# BigBus_Error.net
KiCad netlist of a schematic drawn in EAGLE
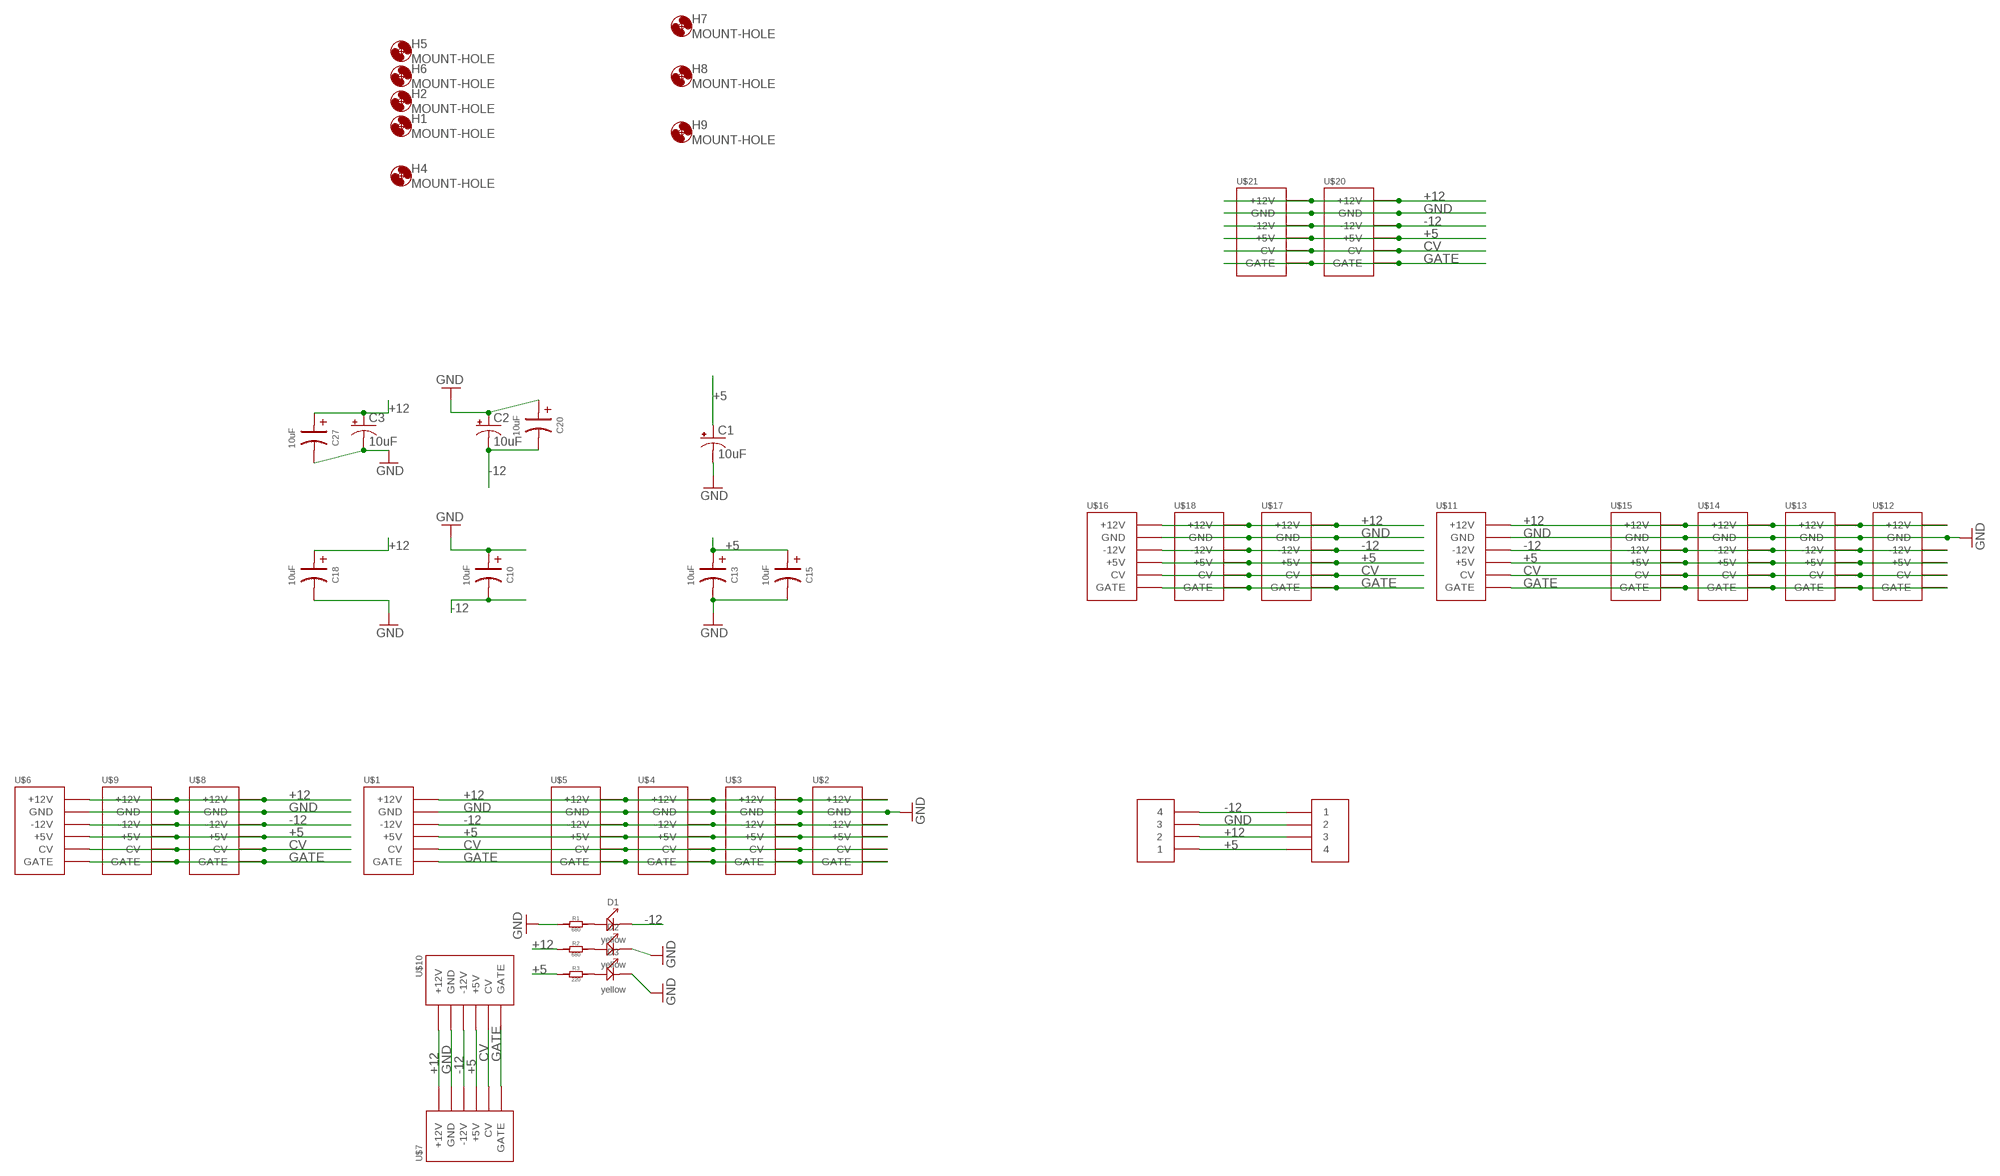
[diagram p0: schematic, sheet 1]

(export (version "E")
  (design (tool "Eeschema 10.0.6"))
  (components
    (comp (ref "C1")
      (value "10uF")
      (footprint "eagle-import:PANASONIC_D")
      (libsource (lib "eagle-import") (part "CAP_POLD"))
    )
    (comp (ref "C2")
      (value "10uF")
      (footprint "eagle-import:PANASONIC_D")
      (libsource (lib "eagle-import") (part "CAP_POLD"))
    )
    (comp (ref "C3")
      (value "10uF")
      (footprint "eagle-import:PANASONIC_D")
      (libsource (lib "eagle-import") (part "CAP_POLD"))
    )
    (comp (ref "C10")
      (value "10uF")
      (footprint "eagle-import:CASE-A_3216")
      (libsource (lib "eagle-import") (part "C-POLAR-A"))
    )
    (comp (ref "C13")
      (value "10uF")
      (footprint "eagle-import:CASE-A_3216")
      (libsource (lib "eagle-import") (part "C-POLAR-A"))
    )
    (comp (ref "C15")
      (value "10uF")
      (footprint "eagle-import:CASE-A_3216")
      (libsource (lib "eagle-import") (part "C-POLAR-A"))
    )
    (comp (ref "C18")
      (value "10uF")
      (footprint "eagle-import:CASE-A_3216")
      (libsource (lib "eagle-import") (part "C-POLAR-A"))
    )
    (comp (ref "C20")
      (value "10uF")
      (footprint "eagle-import:CASE-A_3216")
      (libsource (lib "eagle-import") (part "C-POLAR-A"))
    )
    (comp (ref "C27")
      (value "10uF")
      (footprint "eagle-import:CASE-A_3216")
      (libsource (lib "eagle-import") (part "C-POLAR-A"))
    )
    (comp (ref "D1")
      (value "yellow")
      (footprint "eagle-import:LED0603")
      (libsource (lib "eagle-import") (part "LED"))
    )
    (comp (ref "D2")
      (value "yellow")
      (footprint "eagle-import:LED0603")
      (libsource (lib "eagle-import") (part "LED"))
    )
    (comp (ref "D3")
      (value "yellow")
      (footprint "eagle-import:LED0603")
      (libsource (lib "eagle-import") (part "LED"))
    )
    (comp (ref "H1")
      (value "MOUNT-HOLE")
      (footprint "eagle-import:3.2-NOMARKINGS-SMALLSAFEZONE")
      (libsource (lib "eagle-import") (part "MOUNT-HOLE"))
    )
    (comp (ref "H2")
      (value "MOUNT-HOLE")
      (footprint "eagle-import:3.2-NOMARKINGS-SMALLSAFEZONE")
      (libsource (lib "eagle-import") (part "MOUNT-HOLE"))
    )
    (comp (ref "H4")
      (value "MOUNT-HOLE")
      (footprint "eagle-import:3.2-NOMARKINGS-SMALLSAFEZONE")
      (libsource (lib "eagle-import") (part "MOUNT-HOLE"))
    )
    (comp (ref "H5")
      (value "MOUNT-HOLE")
      (footprint "eagle-import:3.2-NOMARKINGS-SMALLSAFEZONE")
      (libsource (lib "eagle-import") (part "MOUNT-HOLE"))
    )
    (comp (ref "H6")
      (value "MOUNT-HOLE")
      (footprint "eagle-import:3.2-NOMARKINGS-SMALLSAFEZONE")
      (libsource (lib "eagle-import") (part "MOUNT-HOLE"))
    )
    (comp (ref "H7")
      (value "MOUNT-HOLE")
      (footprint "eagle-import:3.2-NOMARKINGS-SMALLSAFEZONE")
      (libsource (lib "eagle-import") (part "MOUNT-HOLE"))
    )
    (comp (ref "H8")
      (value "MOUNT-HOLE")
      (footprint "eagle-import:3.2-NOMARKINGS-SMALLSAFEZONE")
      (libsource (lib "eagle-import") (part "MOUNT-HOLE"))
    )
    (comp (ref "H9")
      (value "MOUNT-HOLE")
      (footprint "eagle-import:3.2-NOMARKINGS-SMALLSAFEZONE")
      (libsource (lib "eagle-import") (part "MOUNT-HOLE"))
    )
    (comp (ref "R1")
      (value "680")
      (footprint "eagle-import:R0603")
      (libsource (lib "eagle-import") (part "R-0603"))
    )
    (comp (ref "R2")
      (value "680")
      (footprint "eagle-import:R0603")
      (libsource (lib "eagle-import") (part "R-0603"))
    )
    (comp (ref "R3")
      (value "220")
      (footprint "eagle-import:R0603")
      (libsource (lib "eagle-import") (part "R-0603"))
    )
    (comp (ref "U$1")
      (value "POWER_SHROUDED_NOTEXT")
      (footprint "eagle-import:POWER_16_SHROUDED_NOTEXT")
      (libsource (lib "eagle-import") (part "POWER_SHROUDED_NOTEXT"))
    )
    (comp (ref "U$2")
      (value "POWER_SHROUDED_NOTEXT")
      (footprint "eagle-import:POWER_16_SHROUDED_NOTEXT")
      (libsource (lib "eagle-import") (part "POWER_SHROUDED_NOTEXT"))
    )
    (comp (ref "U$3")
      (value "POWER_SHROUDED_NOTEXT")
      (footprint "eagle-import:POWER_16_SHROUDED_NOTEXT")
      (libsource (lib "eagle-import") (part "POWER_SHROUDED_NOTEXT"))
    )
    (comp (ref "U$4")
      (value "POWER_SHROUDED_NOTEXT")
      (footprint "eagle-import:POWER_16_SHROUDED_NOTEXT")
      (libsource (lib "eagle-import") (part "POWER_SHROUDED_NOTEXT"))
    )
    (comp (ref "U$5")
      (value "POWER_SHROUDED_NOTEXT")
      (footprint "eagle-import:POWER_16_SHROUDED_NOTEXT")
      (libsource (lib "eagle-import") (part "POWER_SHROUDED_NOTEXT"))
    )
    (comp (ref "U$6")
      (value "POWER_SHROUDED_NOTEXT")
      (footprint "eagle-import:POWER_16_SHROUDED_NOTEXT")
      (libsource (lib "eagle-import") (part "POWER_SHROUDED_NOTEXT"))
    )
    (comp (ref "U$7")
      (value "POWER_SHROUDED_NOTEXT")
      (footprint "eagle-import:POWER_16_SHROUDED_NOTEXT")
      (libsource (lib "eagle-import") (part "POWER_SHROUDED_NOTEXT"))
    )
    (comp (ref "U$8")
      (value "POWER_SHROUDED_NOTEXT")
      (footprint "eagle-import:POWER_16_SHROUDED_NOTEXT")
      (libsource (lib "eagle-import") (part "POWER_SHROUDED_NOTEXT"))
    )
    (comp (ref "U$9")
      (value "POWER_SHROUDED_NOTEXT")
      (footprint "eagle-import:POWER_16_SHROUDED_NOTEXT")
      (libsource (lib "eagle-import") (part "POWER_SHROUDED_NOTEXT"))
    )
    (comp (ref "U$10")
      (value "POWER_SHROUDED_NOTEXT")
      (footprint "eagle-import:POWER_16_SHROUDED_NOTEXT")
      (libsource (lib "eagle-import") (part "POWER_SHROUDED_NOTEXT"))
    )
    (comp (ref "U$11")
      (value "POWER_SHROUDED_NOTEXT")
      (footprint "eagle-import:POWER_16_SHROUDED_NOTEXT")
      (libsource (lib "eagle-import") (part "POWER_SHROUDED_NOTEXT"))
    )
    (comp (ref "U$12")
      (value "POWER_SHROUDED_NOTEXT")
      (footprint "eagle-import:POWER_16_SHROUDED_NOTEXT")
      (libsource (lib "eagle-import") (part "POWER_SHROUDED_NOTEXT"))
    )
    (comp (ref "U$13")
      (value "POWER_SHROUDED_NOTEXT")
      (footprint "eagle-import:POWER_16_SHROUDED_NOTEXT")
      (libsource (lib "eagle-import") (part "POWER_SHROUDED_NOTEXT"))
    )
    (comp (ref "U$14")
      (value "POWER_SHROUDED_NOTEXT")
      (footprint "eagle-import:POWER_16_SHROUDED_NOTEXT")
      (libsource (lib "eagle-import") (part "POWER_SHROUDED_NOTEXT"))
    )
    (comp (ref "U$15")
      (value "POWER_SHROUDED_NOTEXT")
      (footprint "eagle-import:POWER_16_SHROUDED_NOTEXT")
      (libsource (lib "eagle-import") (part "POWER_SHROUDED_NOTEXT"))
    )
    (comp (ref "U$16")
      (value "POWER_SHROUDED_NOTEXT")
      (footprint "eagle-import:POWER_16_SHROUDED_NOTEXT")
      (libsource (lib "eagle-import") (part "POWER_SHROUDED_NOTEXT"))
    )
    (comp (ref "U$17")
      (value "POWER_SHROUDED_NOTEXT")
      (footprint "eagle-import:POWER_16_SHROUDED_NOTEXT")
      (libsource (lib "eagle-import") (part "POWER_SHROUDED_NOTEXT"))
    )
    (comp (ref "U$18")
      (value "POWER_SHROUDED_NOTEXT")
      (footprint "eagle-import:POWER_16_SHROUDED_NOTEXT")
      (libsource (lib "eagle-import") (part "POWER_SHROUDED_NOTEXT"))
    )
    (comp (ref "U$19")
      (value "4PIN5MM")
      (footprint "eagle-import:4PIN5MM")
      (libsource (lib "eagle-import") (part "4PIN5MM"))
    )
    (comp (ref "U$20")
      (value "POWER_SHROUDED_NOTEXT")
      (footprint "eagle-import:POWER_16_SHROUDED_NOTEXT")
      (libsource (lib "eagle-import") (part "POWER_SHROUDED_NOTEXT"))
    )
    (comp (ref "U$21")
      (value "POWER_SHROUDED_NOTEXT")
      (footprint "eagle-import:POWER_16_SHROUDED_NOTEXT")
      (libsource (lib "eagle-import") (part "POWER_SHROUDED_NOTEXT"))
    )
    (comp (ref "U$22")
      (value "4PIN5MM")
      (footprint "eagle-import:4PIN5MM")
      (libsource (lib "eagle-import") (part "4PIN5MM"))
    )
  )
  (nets
    (net (code "1") (name "/+5") (class "Default")
      (node (ref "C1") (pin "+") (pinfunction "+_+") (pintype "passive"))
      (node (ref "C13") (pin "+") (pinfunction "1_+") (pintype "bidirectional"))
      (node (ref "C15") (pin "+") (pinfunction "1_+") (pintype "bidirectional"))
      (node (ref "R3") (pin "1") (pinfunction "1_1") (pintype "bidirectional"))
      (node (ref "U$1") (pin "11") (pinfunction "+5V_11") (pintype "bidirectional"))
      (node (ref "U$1") (pin "12") (pinfunction "+5V_12") (pintype "bidirectional"))
      (node (ref "U$10") (pin "11") (pinfunction "+5V_11") (pintype "bidirectional"))
      (node (ref "U$10") (pin "12") (pinfunction "+5V_12") (pintype "bidirectional"))
      (node (ref "U$11") (pin "11") (pinfunction "+5V_11") (pintype "bidirectional"))
      (node (ref "U$11") (pin "12") (pinfunction "+5V_12") (pintype "bidirectional"))
      (node (ref "U$12") (pin "11") (pinfunction "+5V_11") (pintype "bidirectional"))
      (node (ref "U$12") (pin "12") (pinfunction "+5V_12") (pintype "bidirectional"))
      (node (ref "U$13") (pin "11") (pinfunction "+5V_11") (pintype "bidirectional"))
      (node (ref "U$13") (pin "12") (pinfunction "+5V_12") (pintype "bidirectional"))
      (node (ref "U$14") (pin "11") (pinfunction "+5V_11") (pintype "bidirectional"))
      (node (ref "U$14") (pin "12") (pinfunction "+5V_12") (pintype "bidirectional"))
      (node (ref "U$15") (pin "11") (pinfunction "+5V_11") (pintype "bidirectional"))
      (node (ref "U$15") (pin "12") (pinfunction "+5V_12") (pintype "bidirectional"))
      (node (ref "U$16") (pin "11") (pinfunction "+5V_11") (pintype "bidirectional"))
      (node (ref "U$16") (pin "12") (pinfunction "+5V_12") (pintype "bidirectional"))
      (node (ref "U$17") (pin "11") (pinfunction "+5V_11") (pintype "bidirectional"))
      (node (ref "U$17") (pin "12") (pinfunction "+5V_12") (pintype "bidirectional"))
      (node (ref "U$18") (pin "11") (pinfunction "+5V_11") (pintype "bidirectional"))
      (node (ref "U$18") (pin "12") (pinfunction "+5V_12") (pintype "bidirectional"))
      (node (ref "U$19") (pin "4") (pinfunction "4_4") (pintype "bidirectional"))
      (node (ref "U$2") (pin "11") (pinfunction "+5V_11") (pintype "bidirectional"))
      (node (ref "U$2") (pin "12") (pinfunction "+5V_12") (pintype "bidirectional"))
      (node (ref "U$20") (pin "11") (pinfunction "+5V_11") (pintype "bidirectional"))
      (node (ref "U$20") (pin "12") (pinfunction "+5V_12") (pintype "bidirectional"))
      (node (ref "U$21") (pin "11") (pinfunction "+5V_11") (pintype "bidirectional"))
      (node (ref "U$21") (pin "12") (pinfunction "+5V_12") (pintype "bidirectional"))
      (node (ref "U$22") (pin "1") (pinfunction "1_1") (pintype "bidirectional"))
      (node (ref "U$3") (pin "11") (pinfunction "+5V_11") (pintype "bidirectional"))
      (node (ref "U$3") (pin "12") (pinfunction "+5V_12") (pintype "bidirectional"))
      (node (ref "U$4") (pin "11") (pinfunction "+5V_11") (pintype "bidirectional"))
      (node (ref "U$4") (pin "12") (pinfunction "+5V_12") (pintype "bidirectional"))
      (node (ref "U$5") (pin "11") (pinfunction "+5V_11") (pintype "bidirectional"))
      (node (ref "U$5") (pin "12") (pinfunction "+5V_12") (pintype "bidirectional"))
      (node (ref "U$6") (pin "11") (pinfunction "+5V_11") (pintype "bidirectional"))
      (node (ref "U$6") (pin "12") (pinfunction "+5V_12") (pintype "bidirectional"))
      (node (ref "U$7") (pin "11") (pinfunction "+5V_11") (pintype "bidirectional"))
      (node (ref "U$7") (pin "12") (pinfunction "+5V_12") (pintype "bidirectional"))
      (node (ref "U$8") (pin "11") (pinfunction "+5V_11") (pintype "bidirectional"))
      (node (ref "U$8") (pin "12") (pinfunction "+5V_12") (pintype "bidirectional"))
      (node (ref "U$9") (pin "11") (pinfunction "+5V_11") (pintype "bidirectional"))
      (node (ref "U$9") (pin "12") (pinfunction "+5V_12") (pintype "bidirectional"))
    )
    (net (code "2") (name "/+12") (class "Default")
      (node (ref "C18") (pin "+") (pinfunction "1_+") (pintype "bidirectional"))
      (node (ref "C27") (pin "+") (pinfunction "1_+") (pintype "bidirectional"))
      (node (ref "C3") (pin "+") (pinfunction "+_+") (pintype "passive"))
      (node (ref "R2") (pin "1") (pinfunction "1_1") (pintype "bidirectional"))
      (node (ref "U$1") (pin "10") (pinfunction "+12V_10") (pintype "bidirectional"))
      (node (ref "U$1") (pin "9") (pinfunction "+12V_9") (pintype "bidirectional"))
      (node (ref "U$10") (pin "10") (pinfunction "+12V_10") (pintype "bidirectional"))
      (node (ref "U$10") (pin "9") (pinfunction "+12V_9") (pintype "bidirectional"))
      (node (ref "U$11") (pin "10") (pinfunction "+12V_10") (pintype "bidirectional"))
      (node (ref "U$11") (pin "9") (pinfunction "+12V_9") (pintype "bidirectional"))
      (node (ref "U$12") (pin "10") (pinfunction "+12V_10") (pintype "bidirectional"))
      (node (ref "U$12") (pin "9") (pinfunction "+12V_9") (pintype "bidirectional"))
      (node (ref "U$13") (pin "10") (pinfunction "+12V_10") (pintype "bidirectional"))
      (node (ref "U$13") (pin "9") (pinfunction "+12V_9") (pintype "bidirectional"))
      (node (ref "U$14") (pin "10") (pinfunction "+12V_10") (pintype "bidirectional"))
      (node (ref "U$14") (pin "9") (pinfunction "+12V_9") (pintype "bidirectional"))
      (node (ref "U$15") (pin "10") (pinfunction "+12V_10") (pintype "bidirectional"))
      (node (ref "U$15") (pin "9") (pinfunction "+12V_9") (pintype "bidirectional"))
      (node (ref "U$16") (pin "10") (pinfunction "+12V_10") (pintype "bidirectional"))
      (node (ref "U$16") (pin "9") (pinfunction "+12V_9") (pintype "bidirectional"))
      (node (ref "U$17") (pin "10") (pinfunction "+12V_10") (pintype "bidirectional"))
      (node (ref "U$17") (pin "9") (pinfunction "+12V_9") (pintype "bidirectional"))
      (node (ref "U$18") (pin "10") (pinfunction "+12V_10") (pintype "bidirectional"))
      (node (ref "U$18") (pin "9") (pinfunction "+12V_9") (pintype "bidirectional"))
      (node (ref "U$19") (pin "3") (pinfunction "3_3") (pintype "bidirectional"))
      (node (ref "U$2") (pin "10") (pinfunction "+12V_10") (pintype "bidirectional"))
      (node (ref "U$2") (pin "9") (pinfunction "+12V_9") (pintype "bidirectional"))
      (node (ref "U$20") (pin "10") (pinfunction "+12V_10") (pintype "bidirectional"))
      (node (ref "U$20") (pin "9") (pinfunction "+12V_9") (pintype "bidirectional"))
      (node (ref "U$21") (pin "10") (pinfunction "+12V_10") (pintype "bidirectional"))
      (node (ref "U$21") (pin "9") (pinfunction "+12V_9") (pintype "bidirectional"))
      (node (ref "U$22") (pin "2") (pinfunction "2_2") (pintype "bidirectional"))
      (node (ref "U$3") (pin "10") (pinfunction "+12V_10") (pintype "bidirectional"))
      (node (ref "U$3") (pin "9") (pinfunction "+12V_9") (pintype "bidirectional"))
      (node (ref "U$4") (pin "10") (pinfunction "+12V_10") (pintype "bidirectional"))
      (node (ref "U$4") (pin "9") (pinfunction "+12V_9") (pintype "bidirectional"))
      (node (ref "U$5") (pin "10") (pinfunction "+12V_10") (pintype "bidirectional"))
      (node (ref "U$5") (pin "9") (pinfunction "+12V_9") (pintype "bidirectional"))
      (node (ref "U$6") (pin "10") (pinfunction "+12V_10") (pintype "bidirectional"))
      (node (ref "U$6") (pin "9") (pinfunction "+12V_9") (pintype "bidirectional"))
      (node (ref "U$7") (pin "10") (pinfunction "+12V_10") (pintype "bidirectional"))
      (node (ref "U$7") (pin "9") (pinfunction "+12V_9") (pintype "bidirectional"))
      (node (ref "U$8") (pin "10") (pinfunction "+12V_10") (pintype "bidirectional"))
      (node (ref "U$8") (pin "9") (pinfunction "+12V_9") (pintype "bidirectional"))
      (node (ref "U$9") (pin "10") (pinfunction "+12V_10") (pintype "bidirectional"))
      (node (ref "U$9") (pin "9") (pinfunction "+12V_9") (pintype "bidirectional"))
    )
    (net (code "3") (name "/-12") (class "Default")
      (node (ref "C10") (pin "-") (pinfunction "2_-") (pintype "bidirectional"))
      (node (ref "C2") (pin "-") (pinfunction "-_-") (pintype "passive"))
      (node (ref "C20") (pin "-") (pinfunction "2_-") (pintype "bidirectional"))
      (node (ref "D1") (pin "-") (pinfunction "-_-") (pintype "passive"))
      (node (ref "U$1") (pin "1") (pinfunction "-12V_1") (pintype "bidirectional"))
      (node (ref "U$1") (pin "2") (pinfunction "-12V_2") (pintype "bidirectional"))
      (node (ref "U$10") (pin "1") (pinfunction "-12V_1") (pintype "bidirectional"))
      (node (ref "U$10") (pin "2") (pinfunction "-12V_2") (pintype "bidirectional"))
      (node (ref "U$11") (pin "1") (pinfunction "-12V_1") (pintype "bidirectional"))
      (node (ref "U$11") (pin "2") (pinfunction "-12V_2") (pintype "bidirectional"))
      (node (ref "U$12") (pin "1") (pinfunction "-12V_1") (pintype "bidirectional"))
      (node (ref "U$12") (pin "2") (pinfunction "-12V_2") (pintype "bidirectional"))
      (node (ref "U$13") (pin "1") (pinfunction "-12V_1") (pintype "bidirectional"))
      (node (ref "U$13") (pin "2") (pinfunction "-12V_2") (pintype "bidirectional"))
      (node (ref "U$14") (pin "1") (pinfunction "-12V_1") (pintype "bidirectional"))
      (node (ref "U$14") (pin "2") (pinfunction "-12V_2") (pintype "bidirectional"))
      (node (ref "U$15") (pin "1") (pinfunction "-12V_1") (pintype "bidirectional"))
      (node (ref "U$15") (pin "2") (pinfunction "-12V_2") (pintype "bidirectional"))
      (node (ref "U$16") (pin "1") (pinfunction "-12V_1") (pintype "bidirectional"))
      (node (ref "U$16") (pin "2") (pinfunction "-12V_2") (pintype "bidirectional"))
      (node (ref "U$17") (pin "1") (pinfunction "-12V_1") (pintype "bidirectional"))
      (node (ref "U$17") (pin "2") (pinfunction "-12V_2") (pintype "bidirectional"))
      (node (ref "U$18") (pin "1") (pinfunction "-12V_1") (pintype "bidirectional"))
      (node (ref "U$18") (pin "2") (pinfunction "-12V_2") (pintype "bidirectional"))
      (node (ref "U$19") (pin "1") (pinfunction "1_1") (pintype "bidirectional"))
      (node (ref "U$2") (pin "1") (pinfunction "-12V_1") (pintype "bidirectional"))
      (node (ref "U$2") (pin "2") (pinfunction "-12V_2") (pintype "bidirectional"))
      (node (ref "U$20") (pin "1") (pinfunction "-12V_1") (pintype "bidirectional"))
      (node (ref "U$20") (pin "2") (pinfunction "-12V_2") (pintype "bidirectional"))
      (node (ref "U$21") (pin "1") (pinfunction "-12V_1") (pintype "bidirectional"))
      (node (ref "U$21") (pin "2") (pinfunction "-12V_2") (pintype "bidirectional"))
      (node (ref "U$22") (pin "4") (pinfunction "4_4") (pintype "bidirectional"))
      (node (ref "U$3") (pin "1") (pinfunction "-12V_1") (pintype "bidirectional"))
      (node (ref "U$3") (pin "2") (pinfunction "-12V_2") (pintype "bidirectional"))
      (node (ref "U$4") (pin "1") (pinfunction "-12V_1") (pintype "bidirectional"))
      (node (ref "U$4") (pin "2") (pinfunction "-12V_2") (pintype "bidirectional"))
      (node (ref "U$5") (pin "1") (pinfunction "-12V_1") (pintype "bidirectional"))
      (node (ref "U$5") (pin "2") (pinfunction "-12V_2") (pintype "bidirectional"))
      (node (ref "U$6") (pin "1") (pinfunction "-12V_1") (pintype "bidirectional"))
      (node (ref "U$6") (pin "2") (pinfunction "-12V_2") (pintype "bidirectional"))
      (node (ref "U$7") (pin "1") (pinfunction "-12V_1") (pintype "bidirectional"))
      (node (ref "U$7") (pin "2") (pinfunction "-12V_2") (pintype "bidirectional"))
      (node (ref "U$8") (pin "1") (pinfunction "-12V_1") (pintype "bidirectional"))
      (node (ref "U$8") (pin "2") (pinfunction "-12V_2") (pintype "bidirectional"))
      (node (ref "U$9") (pin "1") (pinfunction "-12V_1") (pintype "bidirectional"))
      (node (ref "U$9") (pin "2") (pinfunction "-12V_2") (pintype "bidirectional"))
    )
    (net (code "4") (name "/CV") (class "Default")
      (node (ref "U$1") (pin "13") (pinfunction "CV_13") (pintype "bidirectional"))
      (node (ref "U$1") (pin "14") (pinfunction "CV_14") (pintype "bidirectional"))
      (node (ref "U$10") (pin "13") (pinfunction "CV_13") (pintype "bidirectional"))
      (node (ref "U$10") (pin "14") (pinfunction "CV_14") (pintype "bidirectional"))
      (node (ref "U$11") (pin "13") (pinfunction "CV_13") (pintype "bidirectional"))
      (node (ref "U$11") (pin "14") (pinfunction "CV_14") (pintype "bidirectional"))
      (node (ref "U$12") (pin "13") (pinfunction "CV_13") (pintype "bidirectional"))
      (node (ref "U$12") (pin "14") (pinfunction "CV_14") (pintype "bidirectional"))
      (node (ref "U$13") (pin "13") (pinfunction "CV_13") (pintype "bidirectional"))
      (node (ref "U$13") (pin "14") (pinfunction "CV_14") (pintype "bidirectional"))
      (node (ref "U$14") (pin "13") (pinfunction "CV_13") (pintype "bidirectional"))
      (node (ref "U$14") (pin "14") (pinfunction "CV_14") (pintype "bidirectional"))
      (node (ref "U$15") (pin "13") (pinfunction "CV_13") (pintype "bidirectional"))
      (node (ref "U$15") (pin "14") (pinfunction "CV_14") (pintype "bidirectional"))
      (node (ref "U$16") (pin "13") (pinfunction "CV_13") (pintype "bidirectional"))
      (node (ref "U$16") (pin "14") (pinfunction "CV_14") (pintype "bidirectional"))
      (node (ref "U$17") (pin "13") (pinfunction "CV_13") (pintype "bidirectional"))
      (node (ref "U$17") (pin "14") (pinfunction "CV_14") (pintype "bidirectional"))
      (node (ref "U$18") (pin "13") (pinfunction "CV_13") (pintype "bidirectional"))
      (node (ref "U$18") (pin "14") (pinfunction "CV_14") (pintype "bidirectional"))
      (node (ref "U$2") (pin "13") (pinfunction "CV_13") (pintype "bidirectional"))
      (node (ref "U$2") (pin "14") (pinfunction "CV_14") (pintype "bidirectional"))
      (node (ref "U$20") (pin "13") (pinfunction "CV_13") (pintype "bidirectional"))
      (node (ref "U$20") (pin "14") (pinfunction "CV_14") (pintype "bidirectional"))
      (node (ref "U$21") (pin "13") (pinfunction "CV_13") (pintype "bidirectional"))
      (node (ref "U$21") (pin "14") (pinfunction "CV_14") (pintype "bidirectional"))
      (node (ref "U$3") (pin "13") (pinfunction "CV_13") (pintype "bidirectional"))
      (node (ref "U$3") (pin "14") (pinfunction "CV_14") (pintype "bidirectional"))
      (node (ref "U$4") (pin "13") (pinfunction "CV_13") (pintype "bidirectional"))
      (node (ref "U$4") (pin "14") (pinfunction "CV_14") (pintype "bidirectional"))
      (node (ref "U$5") (pin "13") (pinfunction "CV_13") (pintype "bidirectional"))
      (node (ref "U$5") (pin "14") (pinfunction "CV_14") (pintype "bidirectional"))
      (node (ref "U$6") (pin "13") (pinfunction "CV_13") (pintype "bidirectional"))
      (node (ref "U$6") (pin "14") (pinfunction "CV_14") (pintype "bidirectional"))
      (node (ref "U$7") (pin "13") (pinfunction "CV_13") (pintype "bidirectional"))
      (node (ref "U$7") (pin "14") (pinfunction "CV_14") (pintype "bidirectional"))
      (node (ref "U$8") (pin "13") (pinfunction "CV_13") (pintype "bidirectional"))
      (node (ref "U$8") (pin "14") (pinfunction "CV_14") (pintype "bidirectional"))
      (node (ref "U$9") (pin "13") (pinfunction "CV_13") (pintype "bidirectional"))
      (node (ref "U$9") (pin "14") (pinfunction "CV_14") (pintype "bidirectional"))
    )
    (net (code "5") (name "/GATE") (class "Default")
      (node (ref "U$1") (pin "15") (pinfunction "GATE_15") (pintype "bidirectional"))
      (node (ref "U$1") (pin "16") (pinfunction "GATE_16") (pintype "bidirectional"))
      (node (ref "U$10") (pin "15") (pinfunction "GATE_15") (pintype "bidirectional"))
      (node (ref "U$10") (pin "16") (pinfunction "GATE_16") (pintype "bidirectional"))
      (node (ref "U$11") (pin "15") (pinfunction "GATE_15") (pintype "bidirectional"))
      (node (ref "U$11") (pin "16") (pinfunction "GATE_16") (pintype "bidirectional"))
      (node (ref "U$12") (pin "15") (pinfunction "GATE_15") (pintype "bidirectional"))
      (node (ref "U$12") (pin "16") (pinfunction "GATE_16") (pintype "bidirectional"))
      (node (ref "U$13") (pin "15") (pinfunction "GATE_15") (pintype "bidirectional"))
      (node (ref "U$13") (pin "16") (pinfunction "GATE_16") (pintype "bidirectional"))
      (node (ref "U$14") (pin "15") (pinfunction "GATE_15") (pintype "bidirectional"))
      (node (ref "U$14") (pin "16") (pinfunction "GATE_16") (pintype "bidirectional"))
      (node (ref "U$15") (pin "15") (pinfunction "GATE_15") (pintype "bidirectional"))
      (node (ref "U$15") (pin "16") (pinfunction "GATE_16") (pintype "bidirectional"))
      (node (ref "U$16") (pin "15") (pinfunction "GATE_15") (pintype "bidirectional"))
      (node (ref "U$16") (pin "16") (pinfunction "GATE_16") (pintype "bidirectional"))
      (node (ref "U$17") (pin "15") (pinfunction "GATE_15") (pintype "bidirectional"))
      (node (ref "U$17") (pin "16") (pinfunction "GATE_16") (pintype "bidirectional"))
      (node (ref "U$18") (pin "15") (pinfunction "GATE_15") (pintype "bidirectional"))
      (node (ref "U$18") (pin "16") (pinfunction "GATE_16") (pintype "bidirectional"))
      (node (ref "U$2") (pin "15") (pinfunction "GATE_15") (pintype "bidirectional"))
      (node (ref "U$2") (pin "16") (pinfunction "GATE_16") (pintype "bidirectional"))
      (node (ref "U$20") (pin "15") (pinfunction "GATE_15") (pintype "bidirectional"))
      (node (ref "U$20") (pin "16") (pinfunction "GATE_16") (pintype "bidirectional"))
      (node (ref "U$21") (pin "15") (pinfunction "GATE_15") (pintype "bidirectional"))
      (node (ref "U$21") (pin "16") (pinfunction "GATE_16") (pintype "bidirectional"))
      (node (ref "U$3") (pin "15") (pinfunction "GATE_15") (pintype "bidirectional"))
      (node (ref "U$3") (pin "16") (pinfunction "GATE_16") (pintype "bidirectional"))
      (node (ref "U$4") (pin "15") (pinfunction "GATE_15") (pintype "bidirectional"))
      (node (ref "U$4") (pin "16") (pinfunction "GATE_16") (pintype "bidirectional"))
      (node (ref "U$5") (pin "15") (pinfunction "GATE_15") (pintype "bidirectional"))
      (node (ref "U$5") (pin "16") (pinfunction "GATE_16") (pintype "bidirectional"))
      (node (ref "U$6") (pin "15") (pinfunction "GATE_15") (pintype "bidirectional"))
      (node (ref "U$6") (pin "16") (pinfunction "GATE_16") (pintype "bidirectional"))
      (node (ref "U$7") (pin "15") (pinfunction "GATE_15") (pintype "bidirectional"))
      (node (ref "U$7") (pin "16") (pinfunction "GATE_16") (pintype "bidirectional"))
      (node (ref "U$8") (pin "15") (pinfunction "GATE_15") (pintype "bidirectional"))
      (node (ref "U$8") (pin "16") (pinfunction "GATE_16") (pintype "bidirectional"))
      (node (ref "U$9") (pin "15") (pinfunction "GATE_15") (pintype "bidirectional"))
      (node (ref "U$9") (pin "16") (pinfunction "GATE_16") (pintype "bidirectional"))
    )
    (net (code "6") (name "GND") (class "Default")
      (node (ref "C1") (pin "-") (pinfunction "-_-") (pintype "passive"))
      (node (ref "C10") (pin "+") (pinfunction "1_+") (pintype "bidirectional"))
      (node (ref "C13") (pin "-") (pinfunction "2_-") (pintype "bidirectional"))
      (node (ref "C15") (pin "-") (pinfunction "2_-") (pintype "bidirectional"))
      (node (ref "C18") (pin "-") (pinfunction "2_-") (pintype "bidirectional"))
      (node (ref "C2") (pin "+") (pinfunction "+_+") (pintype "passive"))
      (node (ref "C20") (pin "+") (pinfunction "1_+") (pintype "bidirectional"))
      (node (ref "C27") (pin "-") (pinfunction "2_-") (pintype "bidirectional"))
      (node (ref "C3") (pin "-") (pinfunction "-_-") (pintype "passive"))
      (node (ref "D2") (pin "-") (pinfunction "-_-") (pintype "passive"))
      (node (ref "D3") (pin "-") (pinfunction "-_-") (pintype "passive"))
      (node (ref "R1") (pin "1") (pinfunction "1_1") (pintype "bidirectional"))
      (node (ref "U$1") (pin "3") (pinfunction "GND_3") (pintype "bidirectional"))
      (node (ref "U$1") (pin "4") (pinfunction "GND_4") (pintype "bidirectional"))
      (node (ref "U$1") (pin "5") (pinfunction "GND_5") (pintype "bidirectional"))
      (node (ref "U$1") (pin "6") (pinfunction "GND_6") (pintype "bidirectional"))
      (node (ref "U$1") (pin "7") (pinfunction "GND_7") (pintype "bidirectional"))
      (node (ref "U$1") (pin "8") (pinfunction "GND_8") (pintype "bidirectional"))
      (node (ref "U$10") (pin "3") (pinfunction "GND_3") (pintype "bidirectional"))
      (node (ref "U$10") (pin "4") (pinfunction "GND_4") (pintype "bidirectional"))
      (node (ref "U$10") (pin "5") (pinfunction "GND_5") (pintype "bidirectional"))
      (node (ref "U$10") (pin "6") (pinfunction "GND_6") (pintype "bidirectional"))
      (node (ref "U$10") (pin "7") (pinfunction "GND_7") (pintype "bidirectional"))
      (node (ref "U$10") (pin "8") (pinfunction "GND_8") (pintype "bidirectional"))
      (node (ref "U$11") (pin "3") (pinfunction "GND_3") (pintype "bidirectional"))
      (node (ref "U$11") (pin "4") (pinfunction "GND_4") (pintype "bidirectional"))
      (node (ref "U$11") (pin "5") (pinfunction "GND_5") (pintype "bidirectional"))
      (node (ref "U$11") (pin "6") (pinfunction "GND_6") (pintype "bidirectional"))
      (node (ref "U$11") (pin "7") (pinfunction "GND_7") (pintype "bidirectional"))
      (node (ref "U$11") (pin "8") (pinfunction "GND_8") (pintype "bidirectional"))
      (node (ref "U$12") (pin "3") (pinfunction "GND_3") (pintype "bidirectional"))
      (node (ref "U$12") (pin "4") (pinfunction "GND_4") (pintype "bidirectional"))
      (node (ref "U$12") (pin "5") (pinfunction "GND_5") (pintype "bidirectional"))
      (node (ref "U$12") (pin "6") (pinfunction "GND_6") (pintype "bidirectional"))
      (node (ref "U$12") (pin "7") (pinfunction "GND_7") (pintype "bidirectional"))
      (node (ref "U$12") (pin "8") (pinfunction "GND_8") (pintype "bidirectional"))
      (node (ref "U$13") (pin "3") (pinfunction "GND_3") (pintype "bidirectional"))
      (node (ref "U$13") (pin "4") (pinfunction "GND_4") (pintype "bidirectional"))
      (node (ref "U$13") (pin "5") (pinfunction "GND_5") (pintype "bidirectional"))
      (node (ref "U$13") (pin "6") (pinfunction "GND_6") (pintype "bidirectional"))
      (node (ref "U$13") (pin "7") (pinfunction "GND_7") (pintype "bidirectional"))
      (node (ref "U$13") (pin "8") (pinfunction "GND_8") (pintype "bidirectional"))
      (node (ref "U$14") (pin "3") (pinfunction "GND_3") (pintype "bidirectional"))
      (node (ref "U$14") (pin "4") (pinfunction "GND_4") (pintype "bidirectional"))
      (node (ref "U$14") (pin "5") (pinfunction "GND_5") (pintype "bidirectional"))
      (node (ref "U$14") (pin "6") (pinfunction "GND_6") (pintype "bidirectional"))
      (node (ref "U$14") (pin "7") (pinfunction "GND_7") (pintype "bidirectional"))
      (node (ref "U$14") (pin "8") (pinfunction "GND_8") (pintype "bidirectional"))
      (node (ref "U$15") (pin "3") (pinfunction "GND_3") (pintype "bidirectional"))
      (node (ref "U$15") (pin "4") (pinfunction "GND_4") (pintype "bidirectional"))
      (node (ref "U$15") (pin "5") (pinfunction "GND_5") (pintype "bidirectional"))
      (node (ref "U$15") (pin "6") (pinfunction "GND_6") (pintype "bidirectional"))
      (node (ref "U$15") (pin "7") (pinfunction "GND_7") (pintype "bidirectional"))
      (node (ref "U$15") (pin "8") (pinfunction "GND_8") (pintype "bidirectional"))
      (node (ref "U$16") (pin "3") (pinfunction "GND_3") (pintype "bidirectional"))
      (node (ref "U$16") (pin "4") (pinfunction "GND_4") (pintype "bidirectional"))
      (node (ref "U$16") (pin "5") (pinfunction "GND_5") (pintype "bidirectional"))
      (node (ref "U$16") (pin "6") (pinfunction "GND_6") (pintype "bidirectional"))
      (node (ref "U$16") (pin "7") (pinfunction "GND_7") (pintype "bidirectional"))
      (node (ref "U$16") (pin "8") (pinfunction "GND_8") (pintype "bidirectional"))
      (node (ref "U$17") (pin "3") (pinfunction "GND_3") (pintype "bidirectional"))
      (node (ref "U$17") (pin "4") (pinfunction "GND_4") (pintype "bidirectional"))
      (node (ref "U$17") (pin "5") (pinfunction "GND_5") (pintype "bidirectional"))
      (node (ref "U$17") (pin "6") (pinfunction "GND_6") (pintype "bidirectional"))
      (node (ref "U$17") (pin "7") (pinfunction "GND_7") (pintype "bidirectional"))
      (node (ref "U$17") (pin "8") (pinfunction "GND_8") (pintype "bidirectional"))
      (node (ref "U$18") (pin "3") (pinfunction "GND_3") (pintype "bidirectional"))
      (node (ref "U$18") (pin "4") (pinfunction "GND_4") (pintype "bidirectional"))
      (node (ref "U$18") (pin "5") (pinfunction "GND_5") (pintype "bidirectional"))
      (node (ref "U$18") (pin "6") (pinfunction "GND_6") (pintype "bidirectional"))
      (node (ref "U$18") (pin "7") (pinfunction "GND_7") (pintype "bidirectional"))
      (node (ref "U$18") (pin "8") (pinfunction "GND_8") (pintype "bidirectional"))
      (node (ref "U$19") (pin "2") (pinfunction "2_2") (pintype "bidirectional"))
      (node (ref "U$2") (pin "3") (pinfunction "GND_3") (pintype "bidirectional"))
      (node (ref "U$2") (pin "4") (pinfunction "GND_4") (pintype "bidirectional"))
      (node (ref "U$2") (pin "5") (pinfunction "GND_5") (pintype "bidirectional"))
      (node (ref "U$2") (pin "6") (pinfunction "GND_6") (pintype "bidirectional"))
      (node (ref "U$2") (pin "7") (pinfunction "GND_7") (pintype "bidirectional"))
      (node (ref "U$2") (pin "8") (pinfunction "GND_8") (pintype "bidirectional"))
      (node (ref "U$20") (pin "3") (pinfunction "GND_3") (pintype "bidirectional"))
      (node (ref "U$20") (pin "4") (pinfunction "GND_4") (pintype "bidirectional"))
      (node (ref "U$20") (pin "5") (pinfunction "GND_5") (pintype "bidirectional"))
      (node (ref "U$20") (pin "6") (pinfunction "GND_6") (pintype "bidirectional"))
      (node (ref "U$20") (pin "7") (pinfunction "GND_7") (pintype "bidirectional"))
      (node (ref "U$20") (pin "8") (pinfunction "GND_8") (pintype "bidirectional"))
      (node (ref "U$21") (pin "3") (pinfunction "GND_3") (pintype "bidirectional"))
      (node (ref "U$21") (pin "4") (pinfunction "GND_4") (pintype "bidirectional"))
      (node (ref "U$21") (pin "5") (pinfunction "GND_5") (pintype "bidirectional"))
      (node (ref "U$21") (pin "6") (pinfunction "GND_6") (pintype "bidirectional"))
      (node (ref "U$21") (pin "7") (pinfunction "GND_7") (pintype "bidirectional"))
      (node (ref "U$21") (pin "8") (pinfunction "GND_8") (pintype "bidirectional"))
      (node (ref "U$22") (pin "3") (pinfunction "3_3") (pintype "bidirectional"))
      (node (ref "U$3") (pin "3") (pinfunction "GND_3") (pintype "bidirectional"))
      (node (ref "U$3") (pin "4") (pinfunction "GND_4") (pintype "bidirectional"))
      (node (ref "U$3") (pin "5") (pinfunction "GND_5") (pintype "bidirectional"))
      (node (ref "U$3") (pin "6") (pinfunction "GND_6") (pintype "bidirectional"))
      (node (ref "U$3") (pin "7") (pinfunction "GND_7") (pintype "bidirectional"))
      (node (ref "U$3") (pin "8") (pinfunction "GND_8") (pintype "bidirectional"))
      (node (ref "U$4") (pin "3") (pinfunction "GND_3") (pintype "bidirectional"))
      (node (ref "U$4") (pin "4") (pinfunction "GND_4") (pintype "bidirectional"))
      (node (ref "U$4") (pin "5") (pinfunction "GND_5") (pintype "bidirectional"))
      (node (ref "U$4") (pin "6") (pinfunction "GND_6") (pintype "bidirectional"))
      (node (ref "U$4") (pin "7") (pinfunction "GND_7") (pintype "bidirectional"))
      (node (ref "U$4") (pin "8") (pinfunction "GND_8") (pintype "bidirectional"))
      (node (ref "U$5") (pin "3") (pinfunction "GND_3") (pintype "bidirectional"))
      (node (ref "U$5") (pin "4") (pinfunction "GND_4") (pintype "bidirectional"))
      (node (ref "U$5") (pin "5") (pinfunction "GND_5") (pintype "bidirectional"))
      (node (ref "U$5") (pin "6") (pinfunction "GND_6") (pintype "bidirectional"))
      (node (ref "U$5") (pin "7") (pinfunction "GND_7") (pintype "bidirectional"))
      (node (ref "U$5") (pin "8") (pinfunction "GND_8") (pintype "bidirectional"))
      (node (ref "U$6") (pin "3") (pinfunction "GND_3") (pintype "bidirectional"))
      (node (ref "U$6") (pin "4") (pinfunction "GND_4") (pintype "bidirectional"))
      (node (ref "U$6") (pin "5") (pinfunction "GND_5") (pintype "bidirectional"))
      (node (ref "U$6") (pin "6") (pinfunction "GND_6") (pintype "bidirectional"))
      (node (ref "U$6") (pin "7") (pinfunction "GND_7") (pintype "bidirectional"))
      (node (ref "U$6") (pin "8") (pinfunction "GND_8") (pintype "bidirectional"))
      (node (ref "U$7") (pin "3") (pinfunction "GND_3") (pintype "bidirectional"))
      (node (ref "U$7") (pin "4") (pinfunction "GND_4") (pintype "bidirectional"))
      (node (ref "U$7") (pin "5") (pinfunction "GND_5") (pintype "bidirectional"))
      (node (ref "U$7") (pin "6") (pinfunction "GND_6") (pintype "bidirectional"))
      (node (ref "U$7") (pin "7") (pinfunction "GND_7") (pintype "bidirectional"))
      (node (ref "U$7") (pin "8") (pinfunction "GND_8") (pintype "bidirectional"))
      (node (ref "U$8") (pin "3") (pinfunction "GND_3") (pintype "bidirectional"))
      (node (ref "U$8") (pin "4") (pinfunction "GND_4") (pintype "bidirectional"))
      (node (ref "U$8") (pin "5") (pinfunction "GND_5") (pintype "bidirectional"))
      (node (ref "U$8") (pin "6") (pinfunction "GND_6") (pintype "bidirectional"))
      (node (ref "U$8") (pin "7") (pinfunction "GND_7") (pintype "bidirectional"))
      (node (ref "U$8") (pin "8") (pinfunction "GND_8") (pintype "bidirectional"))
      (node (ref "U$9") (pin "3") (pinfunction "GND_3") (pintype "bidirectional"))
      (node (ref "U$9") (pin "4") (pinfunction "GND_4") (pintype "bidirectional"))
      (node (ref "U$9") (pin "5") (pinfunction "GND_5") (pintype "bidirectional"))
      (node (ref "U$9") (pin "6") (pinfunction "GND_6") (pintype "bidirectional"))
      (node (ref "U$9") (pin "7") (pinfunction "GND_7") (pintype "bidirectional"))
      (node (ref "U$9") (pin "8") (pinfunction "GND_8") (pintype "bidirectional"))
    )
    (net (code "7") (name "Net-(D1-Pad+)") (class "Default")
      (node (ref "D1") (pin "+") (pinfunction "+_+") (pintype "passive"))
      (node (ref "R1") (pin "2") (pinfunction "2_2") (pintype "bidirectional"))
    )
    (net (code "8") (name "Net-(D2-Pad+)") (class "Default")
      (node (ref "D2") (pin "+") (pinfunction "+_+") (pintype "passive"))
      (node (ref "R2") (pin "2") (pinfunction "2_2") (pintype "bidirectional"))
    )
    (net (code "9") (name "Net-(D3-Pad+)") (class "Default")
      (node (ref "D3") (pin "+") (pinfunction "+_+") (pintype "passive"))
      (node (ref "R3") (pin "2") (pinfunction "2_2") (pintype "bidirectional"))
    )
  )
)
